# Nodino-Cortex-Debug.net
KiCad netlist of a schematic drawn in EAGLE
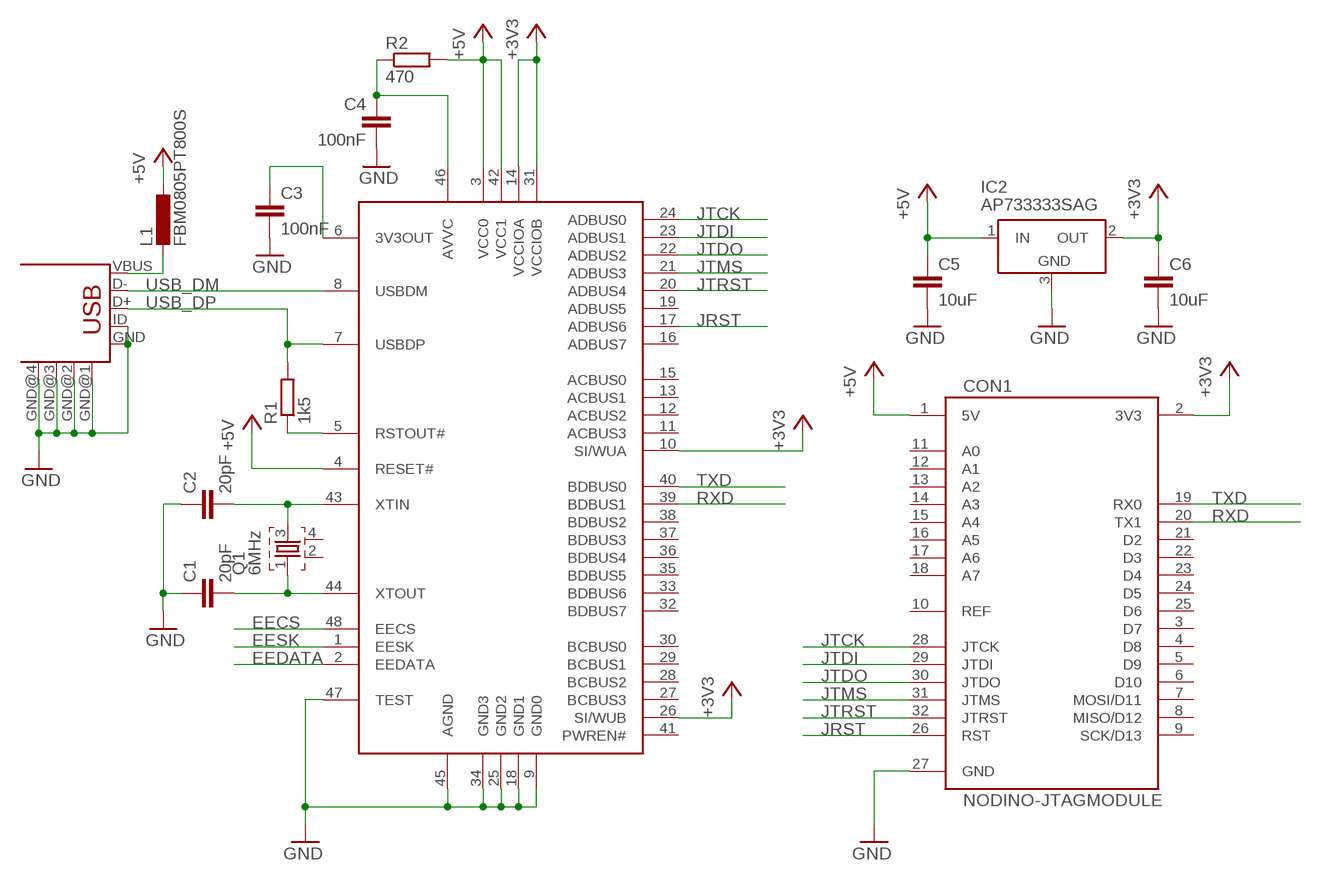
[diagram p0: schematic, sheet 1]

(export (version "E")
  (design (tool "Eeschema 10.0.6"))
  (components
    (comp (ref "C1")
      (value "20pF")
      (footprint "eagle-import:C0603K")
      (libsource (lib "eagle-import") (part "C-EUC0603K"))
    )
    (comp (ref "C2")
      (value "20pF")
      (footprint "eagle-import:C0603K")
      (libsource (lib "eagle-import") (part "C-EUC0603K"))
    )
    (comp (ref "C3")
      (value "100nF")
      (footprint "eagle-import:C0603K")
      (libsource (lib "eagle-import") (part "C-EUC0603K"))
    )
    (comp (ref "C4")
      (value "100nF")
      (footprint "eagle-import:C0603K")
      (libsource (lib "eagle-import") (part "C-EUC0603K"))
    )
    (comp (ref "C5")
      (value "10uF")
      (footprint "eagle-import:C0603K")
      (libsource (lib "eagle-import") (part "C-EUC0603K"))
    )
    (comp (ref "C6")
      (value "10uF")
      (footprint "eagle-import:C0603K")
      (libsource (lib "eagle-import") (part "C-EUC0603K"))
    )
    (comp (ref "CON1")
      (value "NODINO-JTAGMODULE")
      (footprint "eagle-import:NODINO-JTAG-MOD")
      (libsource (lib "eagle-import") (part "NODINO-JTAGMODULE"))
    )
    (comp (ref "CON2")
      (value "USB-OTG_SHIELD")
      (footprint "eagle-import:USB-UAB-S1")
      (libsource (lib "eagle-import") (part "USB-OTG_SHIELD"))
    )
    (comp (ref "IC1")
      (value "FT2232D")
      (footprint "eagle-import:LQFP48")
      (libsource (lib "eagle-import") (part "FT2232C"))
    )
    (comp (ref "IC2")
      (value "AP733333SAG")
      (footprint "eagle-import:SOT23")
      (libsource (lib "eagle-import") (part "AP733333SAG"))
    )
    (comp (ref "L1")
      (value "FBM0805PT800S")
      (footprint "eagle-import:L0805")
      (libsource (lib "eagle-import") (part "L-EUL0805"))
    )
    (comp (ref "Q1")
      (value "6MHz")
      (footprint "eagle-import:FA-20H")
      (libsource (lib "eagle-import") (part "FA-20H"))
    )
    (comp (ref "R1")
      (value "1k5")
      (footprint "eagle-import:R0603K")
      (libsource (lib "eagle-import") (part "R-EU_R0603K"))
    )
    (comp (ref "R2")
      (value "470")
      (footprint "eagle-import:R0603K")
      (libsource (lib "eagle-import") (part "R-EU_R0603K"))
    )
  )
  (nets
    (net (code "1") (name "+3V3") (class "Default")
      (node (ref "C6") (pin "1") (pinfunction "1_1") (pintype "passive"))
      (node (ref "CON1") (pin "2") (pinfunction "3V3_2") (pintype "bidirectional"))
      (node (ref "IC1") (pin "10") (pinfunction "SI/WUA_10") (pintype "bidirectional"))
      (node (ref "IC1") (pin "14") (pinfunction "VCCIOA_14") (pintype "bidirectional"))
      (node (ref "IC1") (pin "26") (pinfunction "SI/WUB_26") (pintype "bidirectional"))
      (node (ref "IC1") (pin "31") (pinfunction "VCCIOB_31") (pintype "bidirectional"))
      (node (ref "IC2") (pin "2") (pinfunction "OUT_2") (pintype "output"))
    )
    (net (code "2") (name "+5V") (class "Default")
      (node (ref "C5") (pin "1") (pinfunction "1_1") (pintype "passive"))
      (node (ref "CON1") (pin "1") (pinfunction "5V_1") (pintype "bidirectional"))
      (node (ref "IC1") (pin "3") (pinfunction "VCC0_3") (pintype "bidirectional"))
      (node (ref "IC1") (pin "4") (pinfunction "RESET#_4") (pintype "bidirectional"))
      (node (ref "IC1") (pin "42") (pinfunction "VCC1_42") (pintype "bidirectional"))
      (node (ref "IC2") (pin "1") (pinfunction "IN_1") (pintype "input"))
      (node (ref "L1") (pin "1") (pinfunction "1_1") (pintype "passive"))
      (node (ref "R2") (pin "2") (pinfunction "2_2") (pintype "passive"))
    )
    (net (code "3") (name "/EECS") (class "Default")
      (node (ref "IC1") (pin "48") (pinfunction "EECS_48") (pintype "bidirectional"))
    )
    (net (code "4") (name "/EEDATA") (class "Default")
      (node (ref "IC1") (pin "2") (pinfunction "EEDATA_2") (pintype "bidirectional"))
    )
    (net (code "5") (name "/EESK") (class "Default")
      (node (ref "IC1") (pin "1") (pinfunction "EESK_1") (pintype "bidirectional"))
    )
    (net (code "6") (name "/JRST") (class "Default")
      (node (ref "CON1") (pin "26") (pinfunction "RST_26") (pintype "bidirectional"))
      (node (ref "IC1") (pin "17") (pinfunction "ADBUS6_17") (pintype "bidirectional"))
    )
    (net (code "7") (name "/JTCK") (class "Default")
      (node (ref "CON1") (pin "28") (pinfunction "JTCK_28") (pintype "bidirectional"))
      (node (ref "IC1") (pin "24") (pinfunction "ADBUS0_24") (pintype "bidirectional"))
    )
    (net (code "8") (name "/JTDI") (class "Default")
      (node (ref "CON1") (pin "29") (pinfunction "JTDI_29") (pintype "bidirectional"))
      (node (ref "IC1") (pin "23") (pinfunction "ADBUS1_23") (pintype "bidirectional"))
    )
    (net (code "9") (name "/JTDO") (class "Default")
      (node (ref "CON1") (pin "30") (pinfunction "JTDO_30") (pintype "bidirectional"))
      (node (ref "IC1") (pin "22") (pinfunction "ADBUS2_22") (pintype "bidirectional"))
    )
    (net (code "10") (name "/JTMS") (class "Default")
      (node (ref "CON1") (pin "31") (pinfunction "JTMS_31") (pintype "bidirectional"))
      (node (ref "IC1") (pin "21") (pinfunction "ADBUS3_21") (pintype "bidirectional"))
    )
    (net (code "11") (name "/JTRST") (class "Default")
      (node (ref "CON1") (pin "32") (pinfunction "JTRST_32") (pintype "bidirectional"))
      (node (ref "IC1") (pin "20") (pinfunction "ADBUS4_20") (pintype "bidirectional"))
    )
    (net (code "12") (name "/RXD") (class "Default")
      (node (ref "CON1") (pin "20") (pinfunction "TX1_20") (pintype "bidirectional"))
      (node (ref "IC1") (pin "39") (pinfunction "BDBUS1_39") (pintype "bidirectional"))
    )
    (net (code "13") (name "/TXD") (class "Default")
      (node (ref "CON1") (pin "19") (pinfunction "RX0_19") (pintype "bidirectional"))
      (node (ref "IC1") (pin "40") (pinfunction "BDBUS0_40") (pintype "bidirectional"))
    )
    (net (code "14") (name "/USB_DM") (class "Default")
      (node (ref "CON2") (pin "D-") (pinfunction "D-_D-") (pintype "bidirectional"))
      (node (ref "IC1") (pin "8") (pinfunction "USBDM_8") (pintype "bidirectional"))
    )
    (net (code "15") (name "/USB_DP") (class "Default")
      (node (ref "CON2") (pin "D+") (pinfunction "D+_D+") (pintype "bidirectional"))
      (node (ref "IC1") (pin "7") (pinfunction "USBDP_7") (pintype "bidirectional"))
      (node (ref "R1") (pin "2") (pinfunction "2_2") (pintype "passive"))
    )
    (net (code "16") (name "GND") (class "Default")
      (node (ref "C1") (pin "1") (pinfunction "1_1") (pintype "passive"))
      (node (ref "C2") (pin "1") (pinfunction "1_1") (pintype "passive"))
      (node (ref "C3") (pin "2") (pinfunction "2_2") (pintype "passive"))
      (node (ref "C4") (pin "2") (pinfunction "2_2") (pintype "passive"))
      (node (ref "C5") (pin "2") (pinfunction "2_2") (pintype "passive"))
      (node (ref "C6") (pin "2") (pinfunction "2_2") (pintype "passive"))
      (node (ref "CON1") (pin "27") (pinfunction "GND_27") (pintype "bidirectional"))
      (node (ref "CON2") (pin "GND") (pinfunction "GND_GND") (pintype "power_in"))
      (node (ref "CON2") (pin "GND@1") (pinfunction "GND_GND@1") (pintype "power_in"))
      (node (ref "CON2") (pin "GND@2") (pinfunction "GND_GND@2") (pintype "power_in"))
      (node (ref "CON2") (pin "GND@3") (pinfunction "GND_GND@3") (pintype "power_in"))
      (node (ref "CON2") (pin "GND@4") (pinfunction "GND_GND@4") (pintype "power_in"))
      (node (ref "CON2") (pin "ID") (pinfunction "ID_ID") (pintype "bidirectional"))
      (node (ref "IC1") (pin "18") (pinfunction "GND1_18") (pintype "bidirectional"))
      (node (ref "IC1") (pin "25") (pinfunction "GND2_25") (pintype "bidirectional"))
      (node (ref "IC1") (pin "34") (pinfunction "GND3_34") (pintype "bidirectional"))
      (node (ref "IC1") (pin "45") (pinfunction "AGND_45") (pintype "bidirectional"))
      (node (ref "IC1") (pin "47") (pinfunction "TEST_47") (pintype "bidirectional"))
      (node (ref "IC1") (pin "9") (pinfunction "GND0_9") (pintype "bidirectional"))
      (node (ref "IC2") (pin "3") (pinfunction "GND_3") (pintype "power_in"))
    )
    (net (code "17") (name "Net-(CON2-PadVBUS)") (class "Default")
      (node (ref "CON2") (pin "VBUS") (pinfunction "VBUS_VBUS") (pintype "power_in"))
      (node (ref "L1") (pin "2") (pinfunction "2_2") (pintype "passive"))
    )
    (net (code "18") (name "Net-(IC1-3V3OUT)") (class "Default")
      (node (ref "C3") (pin "1") (pinfunction "1_1") (pintype "passive"))
      (node (ref "IC1") (pin "6") (pinfunction "3V3OUT_6") (pintype "bidirectional"))
    )
    (net (code "19") (name "Net-(IC1-AVVC)") (class "Default")
      (node (ref "C4") (pin "1") (pinfunction "1_1") (pintype "passive"))
      (node (ref "IC1") (pin "46") (pinfunction "AVVC_46") (pintype "bidirectional"))
      (node (ref "R2") (pin "1") (pinfunction "1_1") (pintype "passive"))
    )
    (net (code "20") (name "Net-(IC1-RSTOUT#)") (class "Default")
      (node (ref "IC1") (pin "5") (pinfunction "RSTOUT#_5") (pintype "bidirectional"))
      (node (ref "R1") (pin "1") (pinfunction "1_1") (pintype "passive"))
    )
    (net (code "21") (name "Net-(IC1-XTIN)") (class "Default")
      (node (ref "C2") (pin "2") (pinfunction "2_2") (pintype "passive"))
      (node (ref "IC1") (pin "43") (pinfunction "XTIN_43") (pintype "bidirectional"))
      (node (ref "Q1") (pin "3") (pinfunction "3_3") (pintype "passive"))
    )
    (net (code "22") (name "Net-(IC1-XTOUT)") (class "Default")
      (node (ref "C1") (pin "2") (pinfunction "2_2") (pintype "passive"))
      (node (ref "IC1") (pin "44") (pinfunction "XTOUT_44") (pintype "bidirectional"))
      (node (ref "Q1") (pin "1") (pinfunction "1_1") (pintype "passive"))
    )
    (net (code "23") (name "unconnected-(CON1-A0-Pad11)") (class "Default")
      (node (ref "CON1") (pin "11") (pinfunction "A0_11") (pintype "bidirectional"))
    )
    (net (code "24") (name "unconnected-(CON1-A1-Pad12)") (class "Default")
      (node (ref "CON1") (pin "12") (pinfunction "A1_12") (pintype "bidirectional"))
    )
    (net (code "25") (name "unconnected-(CON1-A2-Pad13)") (class "Default")
      (node (ref "CON1") (pin "13") (pinfunction "A2_13") (pintype "bidirectional"))
    )
    (net (code "26") (name "unconnected-(CON1-A3-Pad14)") (class "Default")
      (node (ref "CON1") (pin "14") (pinfunction "A3_14") (pintype "bidirectional"))
    )
    (net (code "27") (name "unconnected-(CON1-A4-Pad15)") (class "Default")
      (node (ref "CON1") (pin "15") (pinfunction "A4_15") (pintype "bidirectional"))
    )
    (net (code "28") (name "unconnected-(CON1-A5-Pad16)") (class "Default")
      (node (ref "CON1") (pin "16") (pinfunction "A5_16") (pintype "bidirectional"))
    )
    (net (code "29") (name "unconnected-(CON1-A6-Pad17)") (class "Default")
      (node (ref "CON1") (pin "17") (pinfunction "A6_17") (pintype "bidirectional"))
    )
    (net (code "30") (name "unconnected-(CON1-A7-Pad18)") (class "Default")
      (node (ref "CON1") (pin "18") (pinfunction "A7_18") (pintype "bidirectional"))
    )
    (net (code "31") (name "unconnected-(CON1-D2-Pad21)") (class "Default")
      (node (ref "CON1") (pin "21") (pinfunction "D2_21") (pintype "bidirectional"))
    )
    (net (code "32") (name "unconnected-(CON1-D3-Pad22)") (class "Default")
      (node (ref "CON1") (pin "22") (pinfunction "D3_22") (pintype "bidirectional"))
    )
    (net (code "33") (name "unconnected-(CON1-D4-Pad23)") (class "Default")
      (node (ref "CON1") (pin "23") (pinfunction "D4_23") (pintype "bidirectional"))
    )
    (net (code "34") (name "unconnected-(CON1-D5-Pad24)") (class "Default")
      (node (ref "CON1") (pin "24") (pinfunction "D5_24") (pintype "bidirectional"))
    )
    (net (code "35") (name "unconnected-(CON1-D6-Pad25)") (class "Default")
      (node (ref "CON1") (pin "25") (pinfunction "D6_25") (pintype "bidirectional"))
    )
    (net (code "36") (name "unconnected-(CON1-D7-Pad3)") (class "Default")
      (node (ref "CON1") (pin "3") (pinfunction "D7_3") (pintype "bidirectional"))
    )
    (net (code "37") (name "unconnected-(CON1-D8-Pad4)") (class "Default")
      (node (ref "CON1") (pin "4") (pinfunction "D8_4") (pintype "bidirectional"))
    )
    (net (code "38") (name "unconnected-(CON1-D9-Pad5)") (class "Default")
      (node (ref "CON1") (pin "5") (pinfunction "D9_5") (pintype "bidirectional"))
    )
    (net (code "39") (name "unconnected-(CON1-D10-Pad6)") (class "Default")
      (node (ref "CON1") (pin "6") (pinfunction "D10_6") (pintype "bidirectional"))
    )
    (net (code "40") (name "unconnected-(CON1-MISO{slash}D12-Pad8)") (class "Default")
      (node (ref "CON1") (pin "8") (pinfunction "MISO/D12_8") (pintype "bidirectional"))
    )
    (net (code "41") (name "unconnected-(CON1-MOSI{slash}D11-Pad7)") (class "Default")
      (node (ref "CON1") (pin "7") (pinfunction "MOSI/D11_7") (pintype "bidirectional"))
    )
    (net (code "42") (name "unconnected-(CON1-REF-Pad10)") (class "Default")
      (node (ref "CON1") (pin "10") (pinfunction "REF_10") (pintype "bidirectional"))
    )
    (net (code "43") (name "unconnected-(CON1-SCK{slash}D13-Pad9)") (class "Default")
      (node (ref "CON1") (pin "9") (pinfunction "SCK/D13_9") (pintype "bidirectional"))
    )
    (net (code "44") (name "unconnected-(IC1-ACBUS0-Pad15)") (class "Default")
      (node (ref "IC1") (pin "15") (pinfunction "ACBUS0_15") (pintype "bidirectional"))
    )
    (net (code "45") (name "unconnected-(IC1-ACBUS1-Pad13)") (class "Default")
      (node (ref "IC1") (pin "13") (pinfunction "ACBUS1_13") (pintype "bidirectional"))
    )
    (net (code "46") (name "unconnected-(IC1-ACBUS2-Pad12)") (class "Default")
      (node (ref "IC1") (pin "12") (pinfunction "ACBUS2_12") (pintype "bidirectional"))
    )
    (net (code "47") (name "unconnected-(IC1-ACBUS3-Pad11)") (class "Default")
      (node (ref "IC1") (pin "11") (pinfunction "ACBUS3_11") (pintype "bidirectional"))
    )
    (net (code "48") (name "unconnected-(IC1-ADBUS5-Pad19)") (class "Default")
      (node (ref "IC1") (pin "19") (pinfunction "ADBUS5_19") (pintype "bidirectional"))
    )
    (net (code "49") (name "unconnected-(IC1-ADBUS7-Pad16)") (class "Default")
      (node (ref "IC1") (pin "16") (pinfunction "ADBUS7_16") (pintype "bidirectional"))
    )
    (net (code "50") (name "unconnected-(IC1-BCBUS0-Pad30)") (class "Default")
      (node (ref "IC1") (pin "30") (pinfunction "BCBUS0_30") (pintype "bidirectional"))
    )
    (net (code "51") (name "unconnected-(IC1-BCBUS1-Pad29)") (class "Default")
      (node (ref "IC1") (pin "29") (pinfunction "BCBUS1_29") (pintype "bidirectional"))
    )
    (net (code "52") (name "unconnected-(IC1-BCBUS2-Pad28)") (class "Default")
      (node (ref "IC1") (pin "28") (pinfunction "BCBUS2_28") (pintype "bidirectional"))
    )
    (net (code "53") (name "unconnected-(IC1-BCBUS3-Pad27)") (class "Default")
      (node (ref "IC1") (pin "27") (pinfunction "BCBUS3_27") (pintype "bidirectional"))
    )
    (net (code "54") (name "unconnected-(IC1-BDBUS2-Pad38)") (class "Default")
      (node (ref "IC1") (pin "38") (pinfunction "BDBUS2_38") (pintype "bidirectional"))
    )
    (net (code "55") (name "unconnected-(IC1-BDBUS3-Pad37)") (class "Default")
      (node (ref "IC1") (pin "37") (pinfunction "BDBUS3_37") (pintype "bidirectional"))
    )
    (net (code "56") (name "unconnected-(IC1-BDBUS4-Pad36)") (class "Default")
      (node (ref "IC1") (pin "36") (pinfunction "BDBUS4_36") (pintype "bidirectional"))
    )
    (net (code "57") (name "unconnected-(IC1-BDBUS5-Pad35)") (class "Default")
      (node (ref "IC1") (pin "35") (pinfunction "BDBUS5_35") (pintype "bidirectional"))
    )
    (net (code "58") (name "unconnected-(IC1-BDBUS6-Pad33)") (class "Default")
      (node (ref "IC1") (pin "33") (pinfunction "BDBUS6_33") (pintype "bidirectional"))
    )
    (net (code "59") (name "unconnected-(IC1-BDBUS7-Pad32)") (class "Default")
      (node (ref "IC1") (pin "32") (pinfunction "BDBUS7_32") (pintype "bidirectional"))
    )
    (net (code "60") (name "unconnected-(IC1-PWREN#-Pad41)") (class "Default")
      (node (ref "IC1") (pin "41") (pinfunction "PWREN#_41") (pintype "bidirectional"))
    )
    (net (code "61") (name "unconnected-(Q1-Pad2)") (class "Default")
      (node (ref "Q1") (pin "2") (pinfunction "2_2") (pintype "passive"))
    )
    (net (code "62") (name "unconnected-(Q1-Pad4)") (class "Default")
      (node (ref "Q1") (pin "4") (pinfunction "4_4") (pintype "passive"))
    )
  )
)
